# Yukari_3_11DoF.net
KiCad netlist of a schematic drawn in EAGLE
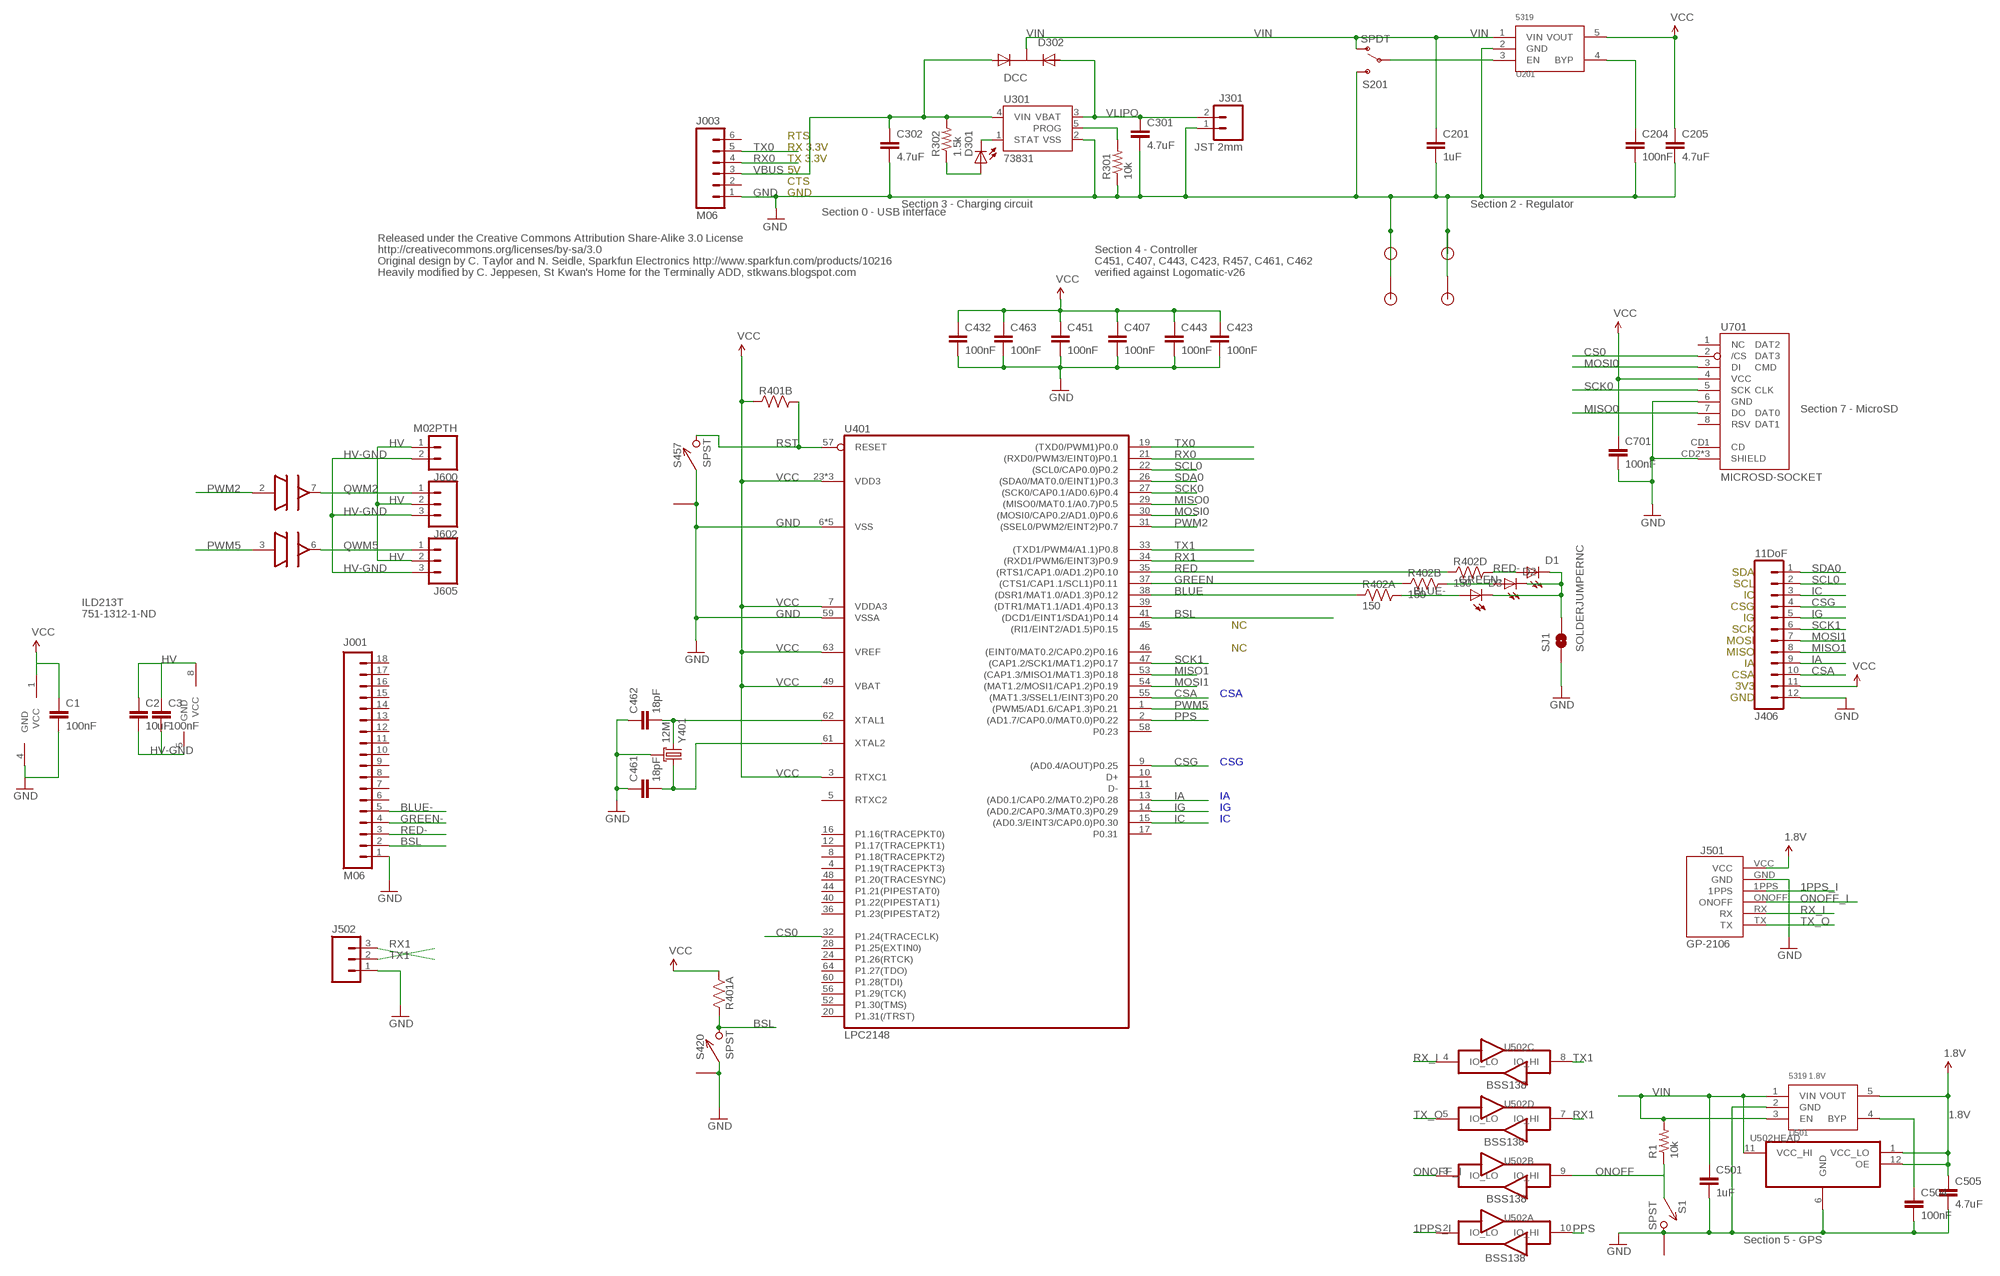
[diagram p0: schematic, sheet 1]

(export (version "E")
  (design (tool "Eeschema 10.0.6"))
  (components
    (comp (ref "C1")
      (value "100nF")
      (footprint "eagle-import:0402-CAP")
      (libsource (lib "eagle-import") (part "CAP0402-CAP"))
    )
    (comp (ref "C2")
      (value "10uF")
      (footprint "eagle-import:1206")
      (libsource (lib "eagle-import") (part "10UF-6.3V-20%(1206)"))
    )
    (comp (ref "C3")
      (value "100nF")
      (footprint "eagle-import:0402-CAP")
      (libsource (lib "eagle-import") (part "CAP0402-CAP"))
    )
    (comp (ref "C201")
      (value "1uF")
      (footprint "eagle-import:0402-CAP")
      (libsource (lib "eagle-import") (part "CAP0402-CAP"))
    )
    (comp (ref "C204")
      (value "100nF")
      (footprint "eagle-import:0402-CAP")
      (libsource (lib "eagle-import") (part "CAP0402-CAP"))
    )
    (comp (ref "C205")
      (value "4.7uF")
      (footprint "eagle-import:0402-CAP")
      (libsource (lib "eagle-import") (part "CAP0402-CAP"))
    )
    (comp (ref "C301")
      (value "4.7uF")
      (footprint "eagle-import:0402-CAP")
      (libsource (lib "eagle-import") (part "CAP0402-CAP"))
    )
    (comp (ref "C302")
      (value "4.7uF")
      (footprint "eagle-import:0402-CAP")
      (libsource (lib "eagle-import") (part "CAP0402-CAP"))
    )
    (comp (ref "C407")
      (value "100nF")
      (footprint "eagle-import:0402-CAP")
      (libsource (lib "eagle-import") (part "CAP0402-CAP"))
    )
    (comp (ref "C423")
      (value "100nF")
      (footprint "eagle-import:0402-CAP")
      (libsource (lib "eagle-import") (part "CAP0402-CAP"))
    )
    (comp (ref "C432")
      (value "100nF")
      (footprint "eagle-import:0402-CAP")
      (libsource (lib "eagle-import") (part "CAP0402-CAP"))
    )
    (comp (ref "C443")
      (value "100nF")
      (footprint "eagle-import:0402-CAP")
      (libsource (lib "eagle-import") (part "CAP0402-CAP"))
    )
    (comp (ref "C451")
      (value "100nF")
      (footprint "eagle-import:0402-CAP")
      (libsource (lib "eagle-import") (part "CAP0402-CAP"))
    )
    (comp (ref "C461")
      (value "18pF")
      (footprint "eagle-import:0402-CAP")
      (libsource (lib "eagle-import") (part "CAP0402-CAP"))
    )
    (comp (ref "C462")
      (value "18pF")
      (footprint "eagle-import:0402-CAP")
      (libsource (lib "eagle-import") (part "CAP0402-CAP"))
    )
    (comp (ref "C463")
      (value "100nF")
      (footprint "eagle-import:0402-CAP")
      (libsource (lib "eagle-import") (part "CAP0402-CAP"))
    )
    (comp (ref "C501")
      (value "1uF")
      (footprint "eagle-import:0402-CAP")
      (libsource (lib "eagle-import") (part "CAP0402-CAP"))
    )
    (comp (ref "C504")
      (value "100nF")
      (footprint "eagle-import:0402-CAP")
      (libsource (lib "eagle-import") (part "CAP0402-CAP"))
    )
    (comp (ref "C505")
      (value "4.7uF")
      (footprint "eagle-import:0402-CAP")
      (libsource (lib "eagle-import") (part "CAP0402-CAP"))
    )
    (comp (ref "C701")
      (value "100nF")
      (footprint "eagle-import:0402-CAP")
      (libsource (lib "eagle-import") (part "CAP0402-CAP"))
    )
    (comp (ref "D1")
      (value "RED")
      (footprint "eagle-import:LED-0603")
      (libsource (lib "eagle-import") (part "LED0603"))
    )
    (comp (ref "D2")
      (value "GREEN")
      (footprint "eagle-import:LED-0603")
      (libsource (lib "eagle-import") (part "LED0603"))
    )
    (comp (ref "D3")
      (value "BLUE")
      (footprint "eagle-import:LED-0603")
      (libsource (lib "eagle-import") (part "LED0603"))
    )
    (comp (ref "D301")
      (value "RED")
      (footprint "eagle-import:LED-0603")
      (libsource (lib "eagle-import") (part "LED0603"))
    )
    (comp (ref "D302")
      (value "DCC")
      (footprint "eagle-import:SOT-23-3")
      (libsource (lib "eagle-import") (part "PMEG2005CT"))
    )
    (comp (ref "J001")
      (value "M06")
      (footprint "eagle-import:1X18")
      (libsource (lib "eagle-import") (part "M18_"))
    )
    (comp (ref "J003")
      (value "M06")
      (footprint "eagle-import:1X06")
      (libsource (lib "eagle-import") (part "M06SIP"))
    )
    (comp (ref "J301")
      (value "JST 2mm")
      (footprint "eagle-import:JST-2-SMD")
      (libsource (lib "eagle-import") (part "M02-JST-2MM-SMT"))
    )
    (comp (ref "J406")
      (value "11DoF")
      (footprint "eagle-import:1X12")
      (libsource (lib "eagle-import") (part "M12PTH"))
    )
    (comp (ref "J501")
      (value "GP-2106")
      (footprint "eagle-import:GP-2106")
      (libsource (lib "eagle-import") (part "GP-2106"))
    )
    (comp (ref "J502")
      (value "M03PTH")
      (footprint "eagle-import:1X03")
      (libsource (lib "eagle-import") (part "M03PTH"))
    )
    (comp (ref "J600")
      (value "M02PTH")
      (footprint "eagle-import:1X02")
      (libsource (lib "eagle-import") (part "SparkFun-Connectors_M02PTH"))
    )
    (comp (ref "J602")
      (value "M03PTH")
      (footprint "eagle-import:1X03")
      (libsource (lib "eagle-import") (part "M03PTH"))
    )
    (comp (ref "J605")
      (value "M03PTH")
      (footprint "eagle-import:1X03")
      (libsource (lib "eagle-import") (part "M03PTH"))
    )
    (comp (ref "JP1")
      (value "STANDOFF")
      (footprint "eagle-import:STANDOFF")
      (libsource (lib "eagle-import") (part "STANDOFF"))
    )
    (comp (ref "JP2")
      (value "STANDOFF")
      (footprint "eagle-import:STANDOFF")
      (libsource (lib "eagle-import") (part "STANDOFF"))
    )
    (comp (ref "JP3")
      (value "STANDOFF")
      (footprint "eagle-import:STANDOFF")
      (libsource (lib "eagle-import") (part "STANDOFF"))
    )
    (comp (ref "JP4")
      (value "STANDOFF")
      (footprint "eagle-import:STANDOFF")
      (libsource (lib "eagle-import") (part "STANDOFF"))
    )
    (comp (ref "R1")
      (value "10k")
      (footprint "eagle-import:0402-RES")
      (libsource (lib "eagle-import") (part "RESISTOR0402-RES"))
    )
    (comp (ref "R301")
      (value "10k")
      (footprint "eagle-import:0402-RES")
      (libsource (lib "eagle-import") (part "RESISTOR0402-RES"))
    )
    (comp (ref "R302")
      (value "1.5k")
      (footprint "eagle-import:0402-RES")
      (libsource (lib "eagle-import") (part "RESISTOR0402-RES"))
    )
    (comp (ref "R401")
      (value "RP2EXB24V")
      (footprint "eagle-import:CRA02")
      (libsource (lib "eagle-import") (part "RP2EXB24V"))
    )
    (comp (ref "R402")
      (value "150")
      (footprint "eagle-import:CRA04")
      (libsource (lib "eagle-import") (part "RP404"))
    )
    (comp (ref "S1")
      (value "SPST")
      (footprint "eagle-import:B3U-1100P")
      (libsource (lib "eagle-import") (part "B3U-1100P"))
    )
    (comp (ref "S201")
      (value "SPDT")
      (footprint "eagle-import:AYZ0202")
      (libsource (lib "eagle-import") (part "SWITCH-SPSTSMD"))
    )
    (comp (ref "S420")
      (value "SPST")
      (footprint "eagle-import:B3U-1100P")
      (libsource (lib "eagle-import") (part "B3U-1100P"))
    )
    (comp (ref "S457")
      (value "SPST")
      (footprint "eagle-import:B3U-1100P")
      (libsource (lib "eagle-import") (part "B3U-1100P"))
    )
    (comp (ref "SJ1")
      (value "SOLDERJUMPERNC")
      (footprint "eagle-import:SJ_2S")
      (libsource (lib "eagle-import") (part "SOLDERJUMPERNC"))
    )
    (comp (ref "U201")
      (value "5319")
      (footprint "eagle-import:SOT-23-5")
      (libsource (lib "eagle-import") (part "MIC5319D5"))
    )
    (comp (ref "U301")
      (value "73831")
      (footprint "eagle-import:SOT23-5")
      (libsource (lib "eagle-import") (part "MCP73831"))
    )
    (comp (ref "U401")
      (value "LPC2148")
      (footprint "eagle-import:LQFP64")
      (libsource (lib "eagle-import") (part "LPC2148"))
    )
    (comp (ref "U501")
      (value "5319 1.8V")
      (footprint "eagle-import:SOT-23-5")
      (libsource (lib "eagle-import") (part "MIC5319D5"))
    )
    (comp (ref "U502")
      (value "TXB0104RUT")
      (footprint "eagle-import:R-PUQFN-N12")
      (libsource (lib "eagle-import") (part "TXB0104RUT"))
    )
    (comp (ref "U600")
      (value "ADUM3221")
      (footprint "eagle-import:SO8N")
      (libsource (lib "eagle-import") (part "ADUM3221"))
    )
    (comp (ref "U701")
      (value "MICROSD-SOCKET")
      (footprint "eagle-import:MICROSD-SOCKET-PP")
      (libsource (lib "eagle-import") (part "MICROSD-SOCKET"))
    )
    (comp (ref "Y401")
      (value "12M")
      (footprint "eagle-import:CRYSTAL_SMD")
      (libsource (lib "eagle-import") (part "TSX-3225"))
    )
  )
  (nets
    (net (code "1") (name "/1PPS_I") (class "Default")
      (node (ref "J501") (pin "1PPS") (pinfunction "1PPS_1PPS") (pintype "bidirectional"))
      (node (ref "U502") (pin "2") (pinfunction "IO_LO_2") (pintype "bidirectional"))
    )
    (net (code "2") (name "/BLUE") (class "Default")
      (node (ref "R402") (pin "1") (pinfunction "1_1") (pintype "passive"))
      (node (ref "U401") (pin "38") (pinfunction "(DSR1/MAT1.0/AD1.3)P0.12_38") (pintype "bidirectional"))
    )
    (net (code "3") (name "/BLUE-") (class "Default")
      (node (ref "D3") (pin "A") (pinfunction "A_A") (pintype "passive"))
      (node (ref "J001") (pin "5") (pinfunction "5_5") (pintype "passive"))
      (node (ref "R402") (pin "8") (pinfunction "2_8") (pintype "passive"))
    )
    (net (code "4") (name "/BSL") (class "Default")
      (node (ref "J001") (pin "2") (pinfunction "2_2") (pintype "passive"))
      (node (ref "R401") (pin "4") (pinfunction "2_4") (pintype "passive"))
      (node (ref "S420") (pin "P$2") (pinfunction "2_P$2") (pintype "bidirectional"))
      (node (ref "U401") (pin "41") (pinfunction "(DCD1/EINT1/SDA1)P0.14_41") (pintype "bidirectional"))
    )
    (net (code "5") (name "/CS0") (class "Default")
      (node (ref "U401") (pin "32") (pinfunction "P1.24(TRACECLK)_32") (pintype "bidirectional"))
      (node (ref "U701") (pin "2") (pinfunction "/CS_2") (pintype "bidirectional"))
    )
    (net (code "6") (name "/CSA") (class "Default")
      (node (ref "J406") (pin "10") (pinfunction "10_10") (pintype "passive"))
      (node (ref "U401") (pin "55") (pinfunction "(MAT1.3/SSEL1/EINT3)P0.20_55") (pintype "bidirectional"))
    )
    (net (code "7") (name "/CSG") (class "Default")
      (node (ref "J406") (pin "4") (pinfunction "4_4") (pintype "passive"))
      (node (ref "U401") (pin "9") (pinfunction "(AD0.4/AOUT)P0.25_9") (pintype "bidirectional"))
    )
    (net (code "8") (name "/GREEN") (class "Default")
      (node (ref "R402") (pin "2") (pinfunction "1_2") (pintype "passive"))
      (node (ref "U401") (pin "37") (pinfunction "(CTS1/CAP1.1/SCL1)P0.11_37") (pintype "bidirectional"))
    )
    (net (code "9") (name "/GREEN-") (class "Default")
      (node (ref "D2") (pin "A") (pinfunction "A_A") (pintype "passive"))
      (node (ref "J001") (pin "4") (pinfunction "4_4") (pintype "passive"))
      (node (ref "R402") (pin "7") (pinfunction "2_7") (pintype "passive"))
    )
    (net (code "10") (name "/HV") (class "Default")
      (node (ref "C2") (pin "1") (pinfunction "1_1") (pintype "passive"))
      (node (ref "C3") (pin "1") (pinfunction "1_1") (pintype "passive"))
      (node (ref "J600") (pin "1") (pinfunction "1_1") (pintype "passive"))
      (node (ref "J602") (pin "2") (pinfunction "2_2") (pintype "passive"))
      (node (ref "J605") (pin "2") (pinfunction "2_2") (pintype "passive"))
      (node (ref "U600") (pin "8") (pinfunction "VCC_8") (pintype "bidirectional"))
    )
    (net (code "11") (name "/HV-GND") (class "Default")
      (node (ref "C2") (pin "2") (pinfunction "2_2") (pintype "passive"))
      (node (ref "C3") (pin "2") (pinfunction "2_2") (pintype "passive"))
      (node (ref "J600") (pin "2") (pinfunction "2_2") (pintype "passive"))
      (node (ref "J602") (pin "3") (pinfunction "3_3") (pintype "passive"))
      (node (ref "J605") (pin "3") (pinfunction "3_3") (pintype "passive"))
      (node (ref "U600") (pin "5") (pinfunction "GND_5") (pintype "bidirectional"))
    )
    (net (code "12") (name "/IA") (class "Default")
      (node (ref "J406") (pin "9") (pinfunction "9_9") (pintype "passive"))
      (node (ref "U401") (pin "13") (pinfunction "(AD0.1/CAP0.2/MAT0.2)P0.28_13") (pintype "bidirectional"))
    )
    (net (code "13") (name "/IC") (class "Default")
      (node (ref "J406") (pin "3") (pinfunction "3_3") (pintype "passive"))
      (node (ref "U401") (pin "15") (pinfunction "(AD0.3/EINT3/CAP0.0)P0.30_15") (pintype "bidirectional"))
    )
    (net (code "14") (name "/IG") (class "Default")
      (node (ref "J406") (pin "5") (pinfunction "5_5") (pintype "passive"))
      (node (ref "U401") (pin "14") (pinfunction "(AD0.2/CAP0.3/MAT0.3)P0.29_14") (pintype "bidirectional"))
    )
    (net (code "15") (name "/MISO0") (class "Default")
      (node (ref "U401") (pin "29") (pinfunction "(MISO0/MAT0.1/A0.7)P0.5_29") (pintype "bidirectional"))
      (node (ref "U701") (pin "7") (pinfunction "DO_7") (pintype "bidirectional"))
    )
    (net (code "16") (name "/MISO1") (class "Default")
      (node (ref "J406") (pin "8") (pinfunction "8_8") (pintype "passive"))
      (node (ref "U401") (pin "53") (pinfunction "(CAP1.3/MISO1/MAT1.3)P0.18_53") (pintype "bidirectional"))
    )
    (net (code "17") (name "/MOSI0") (class "Default")
      (node (ref "U401") (pin "30") (pinfunction "(MOSI0/CAP0.2/AD1.0)P0.6_30") (pintype "bidirectional"))
      (node (ref "U701") (pin "3") (pinfunction "DI_3") (pintype "bidirectional"))
    )
    (net (code "18") (name "/MOSI1") (class "Default")
      (node (ref "J406") (pin "7") (pinfunction "7_7") (pintype "passive"))
      (node (ref "U401") (pin "54") (pinfunction "(MAT1.2/MOSI1/CAP1.2)P0.19_54") (pintype "bidirectional"))
    )
    (net (code "19") (name "/ONOFF") (class "Default")
      (node (ref "R1") (pin "1") (pinfunction "1_1") (pintype "passive"))
      (node (ref "S1") (pin "P$1") (pinfunction "1_P$1") (pintype "bidirectional"))
      (node (ref "U502") (pin "9") (pinfunction "IO_HI_9") (pintype "bidirectional"))
    )
    (net (code "20") (name "/ONOFF_I") (class "Default")
      (node (ref "J501") (pin "ONOFF") (pinfunction "ONOFF_ONOFF") (pintype "bidirectional"))
      (node (ref "U502") (pin "3") (pinfunction "IO_LO_3") (pintype "bidirectional"))
    )
    (net (code "21") (name "/PPS") (class "Default")
      (node (ref "U401") (pin "2") (pinfunction "(AD1.7/CAP0.0/MAT0.0)P0.22_2") (pintype "bidirectional"))
      (node (ref "U502") (pin "10") (pinfunction "IO_HI_10") (pintype "bidirectional"))
    )
    (net (code "22") (name "/PWM2") (class "Default")
      (node (ref "U401") (pin "31") (pinfunction "(SSEL0/PWM2/EINT2)P0.7_31") (pintype "bidirectional"))
      (node (ref "U600") (pin "2") (pinfunction "IN_2") (pintype "input"))
    )
    (net (code "23") (name "/PWM5") (class "Default")
      (node (ref "U401") (pin "1") (pinfunction "(PWM5/AD1.6/CAP1.3)P0.21_1") (pintype "bidirectional"))
      (node (ref "U600") (pin "3") (pinfunction "IN_3") (pintype "input"))
    )
    (net (code "24") (name "/QWM2") (class "Default")
      (node (ref "J602") (pin "1") (pinfunction "1_1") (pintype "passive"))
      (node (ref "U600") (pin "7") (pinfunction "OUT_7") (pintype "bidirectional"))
    )
    (net (code "25") (name "/QWM5") (class "Default")
      (node (ref "J605") (pin "1") (pinfunction "1_1") (pintype "passive"))
      (node (ref "U600") (pin "6") (pinfunction "OUT_6") (pintype "bidirectional"))
    )
    (net (code "26") (name "/RED") (class "Default")
      (node (ref "R402") (pin "4") (pinfunction "1_4") (pintype "passive"))
      (node (ref "U401") (pin "35") (pinfunction "(RTS1/CAP1.0/AD1.2)P0.10_35") (pintype "bidirectional"))
    )
    (net (code "27") (name "/RED-") (class "Default")
      (node (ref "D1") (pin "A") (pinfunction "A_A") (pintype "passive"))
      (node (ref "J001") (pin "3") (pinfunction "3_3") (pintype "passive"))
      (node (ref "R402") (pin "5") (pinfunction "2_5") (pintype "passive"))
    )
    (net (code "28") (name "/RST") (class "Default")
      (node (ref "R401") (pin "3") (pinfunction "2_3") (pintype "passive"))
      (node (ref "S457") (pin "P$2") (pinfunction "2_P$2") (pintype "bidirectional"))
      (node (ref "U401") (pin "57") (pinfunction "RESET_57") (pintype "input"))
    )
    (net (code "29") (name "/RX0") (class "Default")
      (node (ref "J003") (pin "4") (pinfunction "4_4") (pintype "passive"))
      (node (ref "U401") (pin "21") (pinfunction "(RXD0/PWM3/EINT0)P0.1_21") (pintype "bidirectional"))
    )
    (net (code "30") (name "/RX1") (class "Default")
      (node (ref "J502") (pin "2") (pinfunction "2_2") (pintype "passive"))
      (node (ref "U401") (pin "34") (pinfunction "(RXD1/PWM6/EINT3)P0.9_34") (pintype "bidirectional"))
      (node (ref "U502") (pin "7") (pinfunction "IO_HI_7") (pintype "bidirectional"))
    )
    (net (code "31") (name "/RX_I") (class "Default")
      (node (ref "J501") (pin "RX") (pinfunction "RX_RX") (pintype "bidirectional"))
      (node (ref "U502") (pin "4") (pinfunction "IO_LO_4") (pintype "bidirectional"))
    )
    (net (code "32") (name "/SCK0") (class "Default")
      (node (ref "U401") (pin "27") (pinfunction "(SCK0/CAP0.1/AD0.6)P0.4_27") (pintype "bidirectional"))
      (node (ref "U701") (pin "5") (pinfunction "SCK_5") (pintype "bidirectional"))
    )
    (net (code "33") (name "/SCK1") (class "Default")
      (node (ref "J406") (pin "6") (pinfunction "6_6") (pintype "passive"))
      (node (ref "U401") (pin "47") (pinfunction "(CAP1.2/SCK1/MAT1.2)P0.17_47") (pintype "bidirectional"))
    )
    (net (code "34") (name "/SCL0") (class "Default")
      (node (ref "J406") (pin "2") (pinfunction "2_2") (pintype "passive"))
      (node (ref "U401") (pin "22") (pinfunction "(SCL0/CAP0.0)P0.2_22") (pintype "bidirectional"))
    )
    (net (code "35") (name "/SDA0") (class "Default")
      (node (ref "J406") (pin "1") (pinfunction "1_1") (pintype "passive"))
      (node (ref "U401") (pin "26") (pinfunction "(SDA0/MAT0.0/EINT1)P0.3_26") (pintype "bidirectional"))
    )
    (net (code "36") (name "/TX0") (class "Default")
      (node (ref "J003") (pin "5") (pinfunction "5_5") (pintype "passive"))
      (node (ref "U401") (pin "19") (pinfunction "(TXD0/PWM1)P0.0_19") (pintype "bidirectional"))
    )
    (net (code "37") (name "/TX1") (class "Default")
      (node (ref "J502") (pin "3") (pinfunction "3_3") (pintype "passive"))
      (node (ref "U401") (pin "33") (pinfunction "(TXD1/PWM4/A1.1)P0.8_33") (pintype "bidirectional"))
      (node (ref "U502") (pin "8") (pinfunction "IO_HI_8") (pintype "bidirectional"))
    )
    (net (code "38") (name "/TX_O") (class "Default")
      (node (ref "J501") (pin "TX") (pinfunction "TX_TX") (pintype "bidirectional"))
      (node (ref "U502") (pin "5") (pinfunction "IO_LO_5") (pintype "bidirectional"))
    )
    (net (code "39") (name "/VBUS") (class "Default")
      (node (ref "C302") (pin "1") (pinfunction "1_1") (pintype "passive"))
      (node (ref "D302") (pin "1") (pinfunction "A1_1") (pintype "passive"))
      (node (ref "J003") (pin "3") (pinfunction "3_3") (pintype "passive"))
      (node (ref "R302") (pin "2") (pinfunction "2_2") (pintype "passive"))
      (node (ref "U301") (pin "4") (pinfunction "VIN_4") (pintype "power_in"))
    )
    (net (code "40") (name "/VIN") (class "Default")
      (node (ref "C201") (pin "1") (pinfunction "1_1") (pintype "passive"))
      (node (ref "C501") (pin "1") (pinfunction "1_1") (pintype "passive"))
      (node (ref "D302") (pin "3") (pinfunction "K_3") (pintype "passive"))
      (node (ref "R1") (pin "2") (pinfunction "2_2") (pintype "passive"))
      (node (ref "S201") (pin "1") (pinfunction "O_1") (pintype "passive"))
      (node (ref "U201") (pin "1") (pinfunction "VIN_1") (pintype "bidirectional"))
      (node (ref "U501") (pin "1") (pinfunction "VIN_1") (pintype "bidirectional"))
      (node (ref "U501") (pin "3") (pinfunction "EN_3") (pintype "bidirectional"))
      (node (ref "U502") (pin "11") (pinfunction "VCC_HI_11") (pintype "power_in"))
    )
    (net (code "41") (name "/VLIPO") (class "Default")
      (node (ref "C301") (pin "1") (pinfunction "1_1") (pintype "passive"))
      (node (ref "D302") (pin "2") (pinfunction "A2_2") (pintype "passive"))
      (node (ref "J301") (pin "2") (pinfunction "2_2") (pintype "passive"))
      (node (ref "U301") (pin "3") (pinfunction "VBAT_3") (pintype "power_in"))
    )
    (net (code "42") (name "1.8V") (class "Default")
      (node (ref "C505") (pin "1") (pinfunction "1_1") (pintype "passive"))
      (node (ref "J501") (pin "VCC") (pinfunction "VCC_VCC") (pintype "bidirectional"))
      (node (ref "U501") (pin "5") (pinfunction "VOUT_5") (pintype "bidirectional"))
      (node (ref "U502") (pin "1") (pinfunction "VCC_LO_1") (pintype "power_in"))
      (node (ref "U502") (pin "12") (pinfunction "OE_12") (pintype "bidirectional"))
    )
    (net (code "43") (name "GND") (class "Default")
      (node (ref "C1") (pin "2") (pinfunction "2_2") (pintype "passive"))
      (node (ref "C201") (pin "2") (pinfunction "2_2") (pintype "passive"))
      (node (ref "C204") (pin "2") (pinfunction "2_2") (pintype "passive"))
      (node (ref "C205") (pin "2") (pinfunction "2_2") (pintype "passive"))
      (node (ref "C301") (pin "2") (pinfunction "2_2") (pintype "passive"))
      (node (ref "C302") (pin "2") (pinfunction "2_2") (pintype "passive"))
      (node (ref "C407") (pin "2") (pinfunction "2_2") (pintype "passive"))
      (node (ref "C423") (pin "2") (pinfunction "2_2") (pintype "passive"))
      (node (ref "C432") (pin "2") (pinfunction "2_2") (pintype "passive"))
      (node (ref "C443") (pin "2") (pinfunction "2_2") (pintype "passive"))
      (node (ref "C451") (pin "2") (pinfunction "2_2") (pintype "passive"))
      (node (ref "C461") (pin "1") (pinfunction "1_1") (pintype "passive"))
      (node (ref "C462") (pin "1") (pinfunction "1_1") (pintype "passive"))
      (node (ref "C463") (pin "2") (pinfunction "2_2") (pintype "passive"))
      (node (ref "C501") (pin "2") (pinfunction "2_2") (pintype "passive"))
      (node (ref "C504") (pin "2") (pinfunction "2_2") (pintype "passive"))
      (node (ref "C505") (pin "2") (pinfunction "2_2") (pintype "passive"))
      (node (ref "C701") (pin "2") (pinfunction "2_2") (pintype "passive"))
      (node (ref "J001") (pin "1") (pinfunction "1_1") (pintype "passive"))
      (node (ref "J003") (pin "1") (pinfunction "1_1") (pintype "passive"))
      (node (ref "J301") (pin "1") (pinfunction "1_1") (pintype "passive"))
      (node (ref "J406") (pin "12") (pinfunction "12_12") (pintype "passive"))
      (node (ref "J501") (pin "GND") (pinfunction "GND_GND") (pintype "bidirectional"))
      (node (ref "J502") (pin "1") (pinfunction "1_1") (pintype "passive"))
      (node (ref "JP1") (pin "P$1") (pinfunction "P$1_P$1") (pintype "bidirectional"))
      (node (ref "JP2") (pin "P$1") (pinfunction "P$1_P$1") (pintype "bidirectional"))
      (node (ref "JP3") (pin "P$1") (pinfunction "P$1_P$1") (pintype "bidirectional"))
      (node (ref "JP4") (pin "P$1") (pinfunction "P$1_P$1") (pintype "bidirectional"))
      (node (ref "R301") (pin "1") (pinfunction "1_1") (pintype "passive"))
      (node (ref "S1") (pin "P$2") (pinfunction "2_P$2") (pintype "bidirectional"))
      (node (ref "S1") (pin "P$3") (pinfunction "1_P$3") (pintype "bidirectional"))
      (node (ref "S201") (pin "3") (pinfunction "S_3") (pintype "passive"))
      (node (ref "S420") (pin "P$1") (pinfunction "1_P$1") (pintype "bidirectional"))
      (node (ref "S420") (pin "P$3") (pinfunction "1_P$3") (pintype "bidirectional"))
      (node (ref "S457") (pin "P$1") (pinfunction "1_P$1") (pintype "bidirectional"))
      (node (ref "S457") (pin "P$3") (pinfunction "1_P$3") (pintype "bidirectional"))
      (node (ref "SJ1") (pin "1") (pinfunction "1_1") (pintype "passive"))
      (node (ref "U201") (pin "2") (pinfunction "GND_2") (pintype "bidirectional"))
      (node (ref "U301") (pin "2") (pinfunction "VSS_2") (pintype "power_in"))
      (node (ref "U401") (pin "18") (pinfunction "VSS_18") (pintype "power_in"))
      (node (ref "U401") (pin "25") (pinfunction "VSS_25") (pintype "power_in"))
      (node (ref "U401") (pin "42") (pinfunction "VSS_42") (pintype "power_in"))
      (node (ref "U401") (pin "50") (pinfunction "VSS_50") (pintype "power_in"))
      (node (ref "U401") (pin "59") (pinfunction "VSSA_59") (pintype "power_in"))
      (node (ref "U401") (pin "6") (pinfunction "VSS_6") (pintype "power_in"))
      (node (ref "U501") (pin "2") (pinfunction "GND_2") (pintype "bidirectional"))
      (node (ref "U502") (pin "6") (pinfunction "GND_6") (pintype "power_in"))
      (node (ref "U600") (pin "4") (pinfunction "GND_4") (pintype "bidirectional"))
      (node (ref "U701") (pin "6") (pinfunction "GND_6") (pintype "bidirectional"))
      (node (ref "U701") (pin "CD2") (pinfunction "SHIELD_CD2") (pintype "bidirectional"))
      (node (ref "U701") (pin "GND1") (pinfunction "SHIELD_GND1") (pintype "bidirectional"))
      (node (ref "U701") (pin "GND3") (pinfunction "SHIELD_GND3") (pintype "bidirectional"))
      (node (ref "Y401") (pin "2") (pinfunction "GND_2") (pintype "passive"))
      (node (ref "Y401") (pin "4") (pinfunction "GND_4") (pintype "passive"))
    )
    (net (code "44") (name "Net-(D1-PadC)") (class "Default")
      (node (ref "D1") (pin "C") (pinfunction "C_C") (pintype "passive"))
      (node (ref "D2") (pin "C") (pinfunction "C_C") (pintype "passive"))
      (node (ref "D3") (pin "C") (pinfunction "C_C") (pintype "passive"))
      (node (ref "SJ1") (pin "2") (pinfunction "2_2") (pintype "passive"))
    )
    (net (code "45") (name "Net-(D301-PadA)") (class "Default")
      (node (ref "D301") (pin "A") (pinfunction "A_A") (pintype "passive"))
      (node (ref "R302") (pin "1") (pinfunction "1_1") (pintype "passive"))
    )
    (net (code "46") (name "Net-(S201-P)") (class "Default")
      (node (ref "S201") (pin "2") (pinfunction "P_2") (pintype "passive"))
      (node (ref "U201") (pin "3") (pinfunction "EN_3") (pintype "bidirectional"))
    )
    (net (code "47") (name "Net-(U201-BYP)") (class "Default")
      (node (ref "C204") (pin "1") (pinfunction "1_1") (pintype "passive"))
      (node (ref "U201") (pin "4") (pinfunction "BYP_4") (pintype "bidirectional"))
    )
    (net (code "48") (name "Net-(U301-PROG)") (class "Default")
      (node (ref "R301") (pin "2") (pinfunction "2_2") (pintype "passive"))
      (node (ref "U301") (pin "5") (pinfunction "PROG_5") (pintype "input"))
    )
    (net (code "49") (name "Net-(U301-STAT)") (class "Default")
      (node (ref "D301") (pin "C") (pinfunction "C_C") (pintype "passive"))
      (node (ref "U301") (pin "1") (pinfunction "STAT_1") (pintype "output"))
    )
    (net (code "50") (name "Net-(U401-XTAL1)") (class "Default")
      (node (ref "C462") (pin "2") (pinfunction "2_2") (pintype "passive"))
      (node (ref "U401") (pin "62") (pinfunction "XTAL1_62") (pintype "input"))
      (node (ref "Y401") (pin "3") (pinfunction "2_3") (pintype "passive"))
    )
    (net (code "51") (name "Net-(U401-XTAL2)") (class "Default")
      (node (ref "C461") (pin "2") (pinfunction "2_2") (pintype "passive"))
      (node (ref "U401") (pin "61") (pinfunction "XTAL2_61") (pintype "output"))
      (node (ref "Y401") (pin "1") (pinfunction "1_1") (pintype "passive"))
    )
    (net (code "52") (name "Net-(U501-BYP)") (class "Default")
      (node (ref "C504") (pin "1") (pinfunction "1_1") (pintype "passive"))
      (node (ref "U501") (pin "4") (pinfunction "BYP_4") (pintype "bidirectional"))
    )
    (net (code "53") (name "VCC") (class "Default")
      (node (ref "C1") (pin "1") (pinfunction "1_1") (pintype "passive"))
      (node (ref "C205") (pin "1") (pinfunction "1_1") (pintype "passive"))
      (node (ref "C407") (pin "1") (pinfunction "1_1") (pintype "passive"))
      (node (ref "C423") (pin "1") (pinfunction "1_1") (pintype "passive"))
      (node (ref "C432") (pin "1") (pinfunction "1_1") (pintype "passive"))
      (node (ref "C443") (pin "1") (pinfunction "1_1") (pintype "passive"))
      (node (ref "C451") (pin "1") (pinfunction "1_1") (pintype "passive"))
      (node (ref "C463") (pin "1") (pinfunction "1_1") (pintype "passive"))
      (node (ref "C701") (pin "1") (pinfunction "1_1") (pintype "passive"))
      (node (ref "J406") (pin "11") (pinfunction "11_11") (pintype "passive"))
      (node (ref "R401") (pin "1") (pinfunction "1_1") (pintype "passive"))
      (node (ref "R401") (pin "2") (pinfunction "1_2") (pintype "passive"))
      (node (ref "U201") (pin "5") (pinfunction "VOUT_5") (pintype "bidirectional"))
      (node (ref "U401") (pin "23") (pinfunction "VDD3_23") (pintype "power_in"))
      (node (ref "U401") (pin "3") (pinfunction "RTXC1_3") (pintype "input"))
      (node (ref "U401") (pin "43") (pinfunction "VDD3_43") (pintype "power_in"))
      (node (ref "U401") (pin "49") (pinfunction "VBAT_49") (pintype "power_in"))
      (node (ref "U401") (pin "51") (pinfunction "VDD3_51") (pintype "power_in"))
      (node (ref "U401") (pin "63") (pinfunction "VREF_63") (pintype "input"))
      (node (ref "U401") (pin "7") (pinfunction "VDDA3_7") (pintype "power_in"))
      (node (ref "U600") (pin "1") (pinfunction "VCC_1") (pintype "bidirectional"))
      (node (ref "U701") (pin "4") (pinfunction "VCC_4") (pintype "bidirectional"))
    )
    (net (code "54") (name "unconnected-(J001-Pad6)") (class "Default")
      (node (ref "J001") (pin "6") (pinfunction "6_6") (pintype "passive"))
    )
    (net (code "55") (name "unconnected-(J001-Pad7)") (class "Default")
      (node (ref "J001") (pin "7") (pinfunction "7_7") (pintype "passive"))
    )
    (net (code "56") (name "unconnected-(J001-Pad8)") (class "Default")
      (node (ref "J001") (pin "8") (pinfunction "8_8") (pintype "passive"))
    )
    (net (code "57") (name "unconnected-(J001-Pad9)") (class "Default")
      (node (ref "J001") (pin "9") (pinfunction "9_9") (pintype "passive"))
    )
    (net (code "58") (name "unconnected-(J001-Pad10)") (class "Default")
      (node (ref "J001") (pin "10") (pinfunction "10_10") (pintype "passive"))
    )
    (net (code "59") (name "unconnected-(J001-Pad11)") (class "Default")
      (node (ref "J001") (pin "11") (pinfunction "11_11") (pintype "passive"))
    )
    (net (code "60") (name "unconnected-(J001-Pad12)") (class "Default")
      (node (ref "J001") (pin "12") (pinfunction "12_12") (pintype "passive"))
    )
    (net (code "61") (name "unconnected-(J001-Pad13)") (class "Default")
      (node (ref "J001") (pin "13") (pinfunction "13_13") (pintype "passive"))
    )
    (net (code "62") (name "unconnected-(J001-Pad14)") (class "Default")
      (node (ref "J001") (pin "14") (pinfunction "14_14") (pintype "passive"))
    )
    (net (code "63") (name "unconnected-(J001-Pad15)") (class "Default")
      (node (ref "J001") (pin "15") (pinfunction "15_15") (pintype "passive"))
    )
    (net (code "64") (name "unconnected-(J001-Pad16)") (class "Default")
      (node (ref "J001") (pin "16") (pinfunction "16_16") (pintype "passive"))
    )
    (net (code "65") (name "unconnected-(J001-Pad17)") (class "Default")
      (node (ref "J001") (pin "17") (pinfunction "17_17") (pintype "passive"))
    )
    (net (code "66") (name "unconnected-(J001-Pad18)") (class "Default")
      (node (ref "J001") (pin "18") (pinfunction "18_18") (pintype "passive"))
    )
    (net (code "67") (name "unconnected-(J003-Pad2)") (class "Default")
      (node (ref "J003") (pin "2") (pinfunction "2_2") (pintype "passive"))
    )
    (net (code "68") (name "unconnected-(J003-Pad6)") (class "Default")
      (node (ref "J003") (pin "6") (pinfunction "6_6") (pintype "passive"))
    )
    (net (code "69") (name "unconnected-(U401-(DTR1{slash}MAT1.1{slash}AD1.4)P0.13-Pad39)") (class "Default")
      (node (ref "U401") (pin "39") (pinfunction "(DTR1/MAT1.1/AD1.4)P0.13_39") (pintype "bidirectional"))
    )
    (net (code "70") (name "unconnected-(U401-(EINT0{slash}MAT0.2{slash}CAP0.2)P0.16-Pad46)") (class "Default")
      (node (ref "U401") (pin "46") (pinfunction "(EINT0/MAT0.2/CAP0.2)P0.16_46") (pintype "bidirectional"))
    )
    (net (code "71") (name "unconnected-(U401-(RI1{slash}EINT2{slash}AD1.5)P0.15-Pad45)") (class "Default")
      (node (ref "U401") (pin "45") (pinfunction "(RI1/EINT2/AD1.5)P0.15_45") (pintype "bidirectional"))
    )
    (net (code "72") (name "unconnected-(U401-D+-Pad10)") (class "Default")
      (node (ref "U401") (pin "10") (pinfunction "D+_10") (pintype "bidirectional"))
    )
    (net (code "73") (name "unconnected-(U401-D--Pad11)") (class "Default")
      (node (ref "U401") (pin "11") (pinfunction "D-_11") (pintype "bidirectional"))
    )
    (net (code "74") (name "unconnected-(U401-P0.23-Pad58)") (class "Default")
      (node (ref "U401") (pin "58") (pinfunction "P0.23_58") (pintype "bidirectional"))
    )
    (net (code "75") (name "unconnected-(U401-P0.31-Pad17)") (class "Default")
      (node (ref "U401") (pin "17") (pinfunction "P0.31_17") (pintype "output"))
    )
    (net (code "76") (name "unconnected-(U401-P1.16(TRACEPKT0)-Pad16)") (class "Default")
      (node (ref "U401") (pin "16") (pinfunction "P1.16(TRACEPKT0)_16") (pintype "bidirectional"))
    )
    (net (code "77") (name "unconnected-(U401-P1.17(TRACEPKT1)-Pad12)") (class "Default")
      (node (ref "U401") (pin "12") (pinfunction "P1.17(TRACEPKT1)_12") (pintype "bidirectional"))
    )
    (net (code "78") (name "unconnected-(U401-P1.18(TRACEPKT2)-Pad8)") (class "Default")
      (node (ref "U401") (pin "8") (pinfunction "P1.18(TRACEPKT2)_8") (pintype "bidirectional"))
    )
    (net (code "79") (name "unconnected-(U401-P1.19(TRACEPKT3)-Pad4)") (class "Default")
      (node (ref "U401") (pin "4") (pinfunction "P1.19(TRACEPKT3)_4") (pintype "bidirectional"))
    )
    (net (code "80") (name "unconnected-(U401-P1.20(TRACESYNC)-Pad48)") (class "Default")
      (node (ref "U401") (pin "48") (pinfunction "P1.20(TRACESYNC)_48") (pintype "bidirectional"))
    )
    (net (code "81") (name "unconnected-(U401-P1.21(PIPESTAT0)-Pad44)") (class "Default")
      (node (ref "U401") (pin "44") (pinfunction "P1.21(PIPESTAT0)_44") (pintype "bidirectional"))
    )
    (net (code "82") (name "unconnected-(U401-P1.22(PIPESTAT1)-Pad40)") (class "Default")
      (node (ref "U401") (pin "40") (pinfunction "P1.22(PIPESTAT1)_40") (pintype "bidirectional"))
    )
    (net (code "83") (name "unconnected-(U401-P1.23(PIPESTAT2)-Pad36)") (class "Default")
      (node (ref "U401") (pin "36") (pinfunction "P1.23(PIPESTAT2)_36") (pintype "bidirectional"))
    )
    (net (code "84") (name "unconnected-(U401-P1.25(EXTIN0)-Pad28)") (class "Default")
      (node (ref "U401") (pin "28") (pinfunction "P1.25(EXTIN0)_28") (pintype "bidirectional"))
    )
    (net (code "85") (name "unconnected-(U401-P1.26(RTCK)-Pad24)") (class "Default")
      (node (ref "U401") (pin "24") (pinfunction "P1.26(RTCK)_24") (pintype "bidirectional"))
    )
    (net (code "86") (name "unconnected-(U401-P1.27(TDO)-Pad64)") (class "Default")
      (node (ref "U401") (pin "64") (pinfunction "P1.27(TDO)_64") (pintype "bidirectional"))
    )
    (net (code "87") (name "unconnected-(U401-P1.28(TDI)-Pad60)") (class "Default")
      (node (ref "U401") (pin "60") (pinfunction "P1.28(TDI)_60") (pintype "bidirectional"))
    )
    (net (code "88") (name "unconnected-(U401-P1.29(TCK)-Pad56)") (class "Default")
      (node (ref "U401") (pin "56") (pinfunction "P1.29(TCK)_56") (pintype "bidirectional"))
    )
    (net (code "89") (name "unconnected-(U401-P1.30(TMS)-Pad52)") (class "Default")
      (node (ref "U401") (pin "52") (pinfunction "P1.30(TMS)_52") (pintype "bidirectional"))
    )
    (net (code "90") (name "unconnected-(U401-P1.31({slash}TRST)-Pad20)") (class "Default")
      (node (ref "U401") (pin "20") (pinfunction "P1.31(/TRST)_20") (pintype "bidirectional"))
    )
    (net (code "91") (name "unconnected-(U401-RTXC2-Pad5)") (class "Default")
      (node (ref "U401") (pin "5") (pinfunction "RTXC2_5") (pintype "output"))
    )
    (net (code "92") (name "unconnected-(U701-CD-PadCD1)") (class "Default")
      (node (ref "U701") (pin "CD1") (pinfunction "CD_CD1") (pintype "bidirectional"))
    )
    (net (code "93") (name "unconnected-(U701-NC-Pad1)") (class "Default")
      (node (ref "U701") (pin "1") (pinfunction "NC_1") (pintype "bidirectional"))
    )
    (net (code "94") (name "unconnected-(U701-RSV-Pad8)") (class "Default")
      (node (ref "U701") (pin "8") (pinfunction "RSV_8") (pintype "bidirectional"))
    )
  )
)
